# untitled.net
KiCad netlist of a schematic drawn in EAGLE
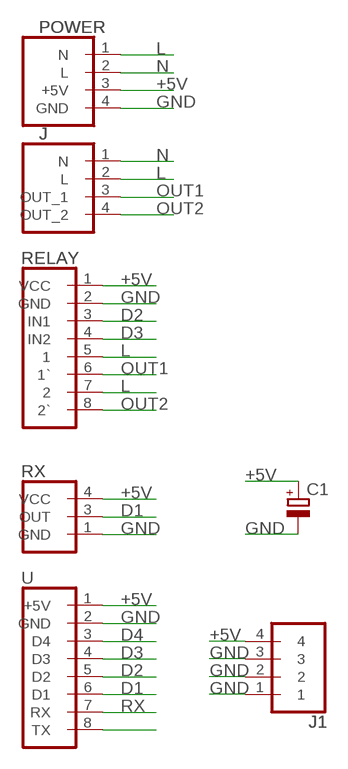
[diagram p0: schematic, sheet 1]

(export (version "E")
  (design (tool "Eeschema 10.0.6"))
  (components
    (comp (ref "C1")
      (value "CPOL-EUE5-5")
      (footprint "eagle-import:E5-5")
      (libsource (lib "eagle-import") (part "CPOL-EUE5-5"))
    )
    (comp (ref "J")
      (value "OUT_HEAD_4_AC_2CH")
      (footprint "eagle-import:OUT_HEAD_4_AC_2CH")
      (libsource (lib "eagle-import") (part "OUT_HEAD_4_AC_2CH"))
    )
    (comp (ref "J1")
      (value "2.544")
      (footprint "eagle-import:2.54_4")
      (libsource (lib "eagle-import") (part "2.544"))
    )
    (comp (ref "POWER")
      (value "AC_DC")
      (footprint "eagle-import:AC_DC_SIDE")
      (libsource (lib "eagle-import") (part "AC_DC"))
    )
    (comp (ref "RELAY")
      (value "2_SOLID_RELAY")
      (footprint "eagle-import:2_SOLID_RELAY")
      (libsource (lib "eagle-import") (part "2_SOLID_RELAY"))
    )
    (comp (ref "RX")
      (value "315MHZ_RX_UART")
      (footprint "eagle-import:315MHZ_RX_UART")
      (libsource (lib "eagle-import") (part "315MHZ_RX_UART"))
    )
    (comp (ref "U")
      (value "ESP8266_MINI_SIDE")
      (footprint "eagle-import:ESP8266_MINI_SIDE")
      (libsource (lib "eagle-import") (part "ESP8266_MINI_SIDE"))
    )
  )
  (nets
    (net (code "1") (name "/+5V") (class "Default")
      (node (ref "C1") (pin "+") (pinfunction "+_+") (pintype "passive"))
      (node (ref "J1") (pin "4") (pinfunction "4_4") (pintype "bidirectional"))
      (node (ref "POWER") (pin "3") (pinfunction "+5V_3") (pintype "bidirectional"))
      (node (ref "RELAY") (pin "1") (pinfunction "VCC_1") (pintype "bidirectional"))
      (node (ref "RX") (pin "4") (pinfunction "VCC_4") (pintype "bidirectional"))
      (node (ref "U") (pin "1") (pinfunction "+5V_1") (pintype "bidirectional"))
    )
    (net (code "2") (name "/D1") (class "Default")
      (node (ref "RX") (pin "3") (pinfunction "OUT_3") (pintype "bidirectional"))
      (node (ref "U") (pin "6") (pinfunction "D1_6") (pintype "bidirectional"))
    )
    (net (code "3") (name "/D2") (class "Default")
      (node (ref "RELAY") (pin "3") (pinfunction "IN1_3") (pintype "bidirectional"))
      (node (ref "U") (pin "5") (pinfunction "D2_5") (pintype "bidirectional"))
    )
    (net (code "4") (name "/D3") (class "Default")
      (node (ref "RELAY") (pin "4") (pinfunction "IN2_4") (pintype "bidirectional"))
      (node (ref "U") (pin "4") (pinfunction "D3_4") (pintype "bidirectional"))
    )
    (net (code "5") (name "/D4") (class "Default")
      (node (ref "U") (pin "3") (pinfunction "D4_3") (pintype "bidirectional"))
    )
    (net (code "6") (name "/GND") (class "Default")
      (node (ref "C1") (pin "-") (pinfunction "-_-") (pintype "passive"))
      (node (ref "J1") (pin "1") (pinfunction "1_1") (pintype "bidirectional"))
      (node (ref "J1") (pin "2") (pinfunction "2_2") (pintype "bidirectional"))
      (node (ref "J1") (pin "3") (pinfunction "3_3") (pintype "bidirectional"))
      (node (ref "POWER") (pin "4") (pinfunction "GND_4") (pintype "bidirectional"))
      (node (ref "RELAY") (pin "2") (pinfunction "GND_2") (pintype "bidirectional"))
      (node (ref "RX") (pin "1") (pinfunction "GND_1") (pintype "bidirectional"))
      (node (ref "U") (pin "2") (pinfunction "GND_2") (pintype "bidirectional"))
    )
    (net (code "7") (name "/L") (class "Default")
      (node (ref "J") (pin "2") (pinfunction "L_2") (pintype "bidirectional"))
      (node (ref "POWER") (pin "1") (pinfunction "N_1") (pintype "bidirectional"))
      (node (ref "RELAY") (pin "5") (pinfunction "1_5") (pintype "bidirectional"))
      (node (ref "RELAY") (pin "7") (pinfunction "2_7") (pintype "bidirectional"))
    )
    (net (code "8") (name "/N") (class "Default")
      (node (ref "J") (pin "1") (pinfunction "N_1") (pintype "bidirectional"))
      (node (ref "POWER") (pin "2") (pinfunction "L_2") (pintype "bidirectional"))
    )
    (net (code "9") (name "/OUT1") (class "Default")
      (node (ref "J") (pin "3") (pinfunction "OUT_1_3") (pintype "bidirectional"))
      (node (ref "RELAY") (pin "6") (pinfunction "1`_6") (pintype "bidirectional"))
    )
    (net (code "10") (name "/OUT2") (class "Default")
      (node (ref "J") (pin "4") (pinfunction "OUT_2_4") (pintype "bidirectional"))
      (node (ref "RELAY") (pin "8") (pinfunction "2`_8") (pintype "bidirectional"))
    )
    (net (code "11") (name "/RX") (class "Default")
      (node (ref "U") (pin "7") (pinfunction "RX_7") (pintype "bidirectional"))
    )
    (net (code "12") (name "unconnected-(U-TX-Pad8)") (class "Default")
      (node (ref "U") (pin "8") (pinfunction "TX_8") (pintype "bidirectional"))
    )
  )
)
